# BaseCutout.net
KiCad netlist of a schematic drawn in EAGLE
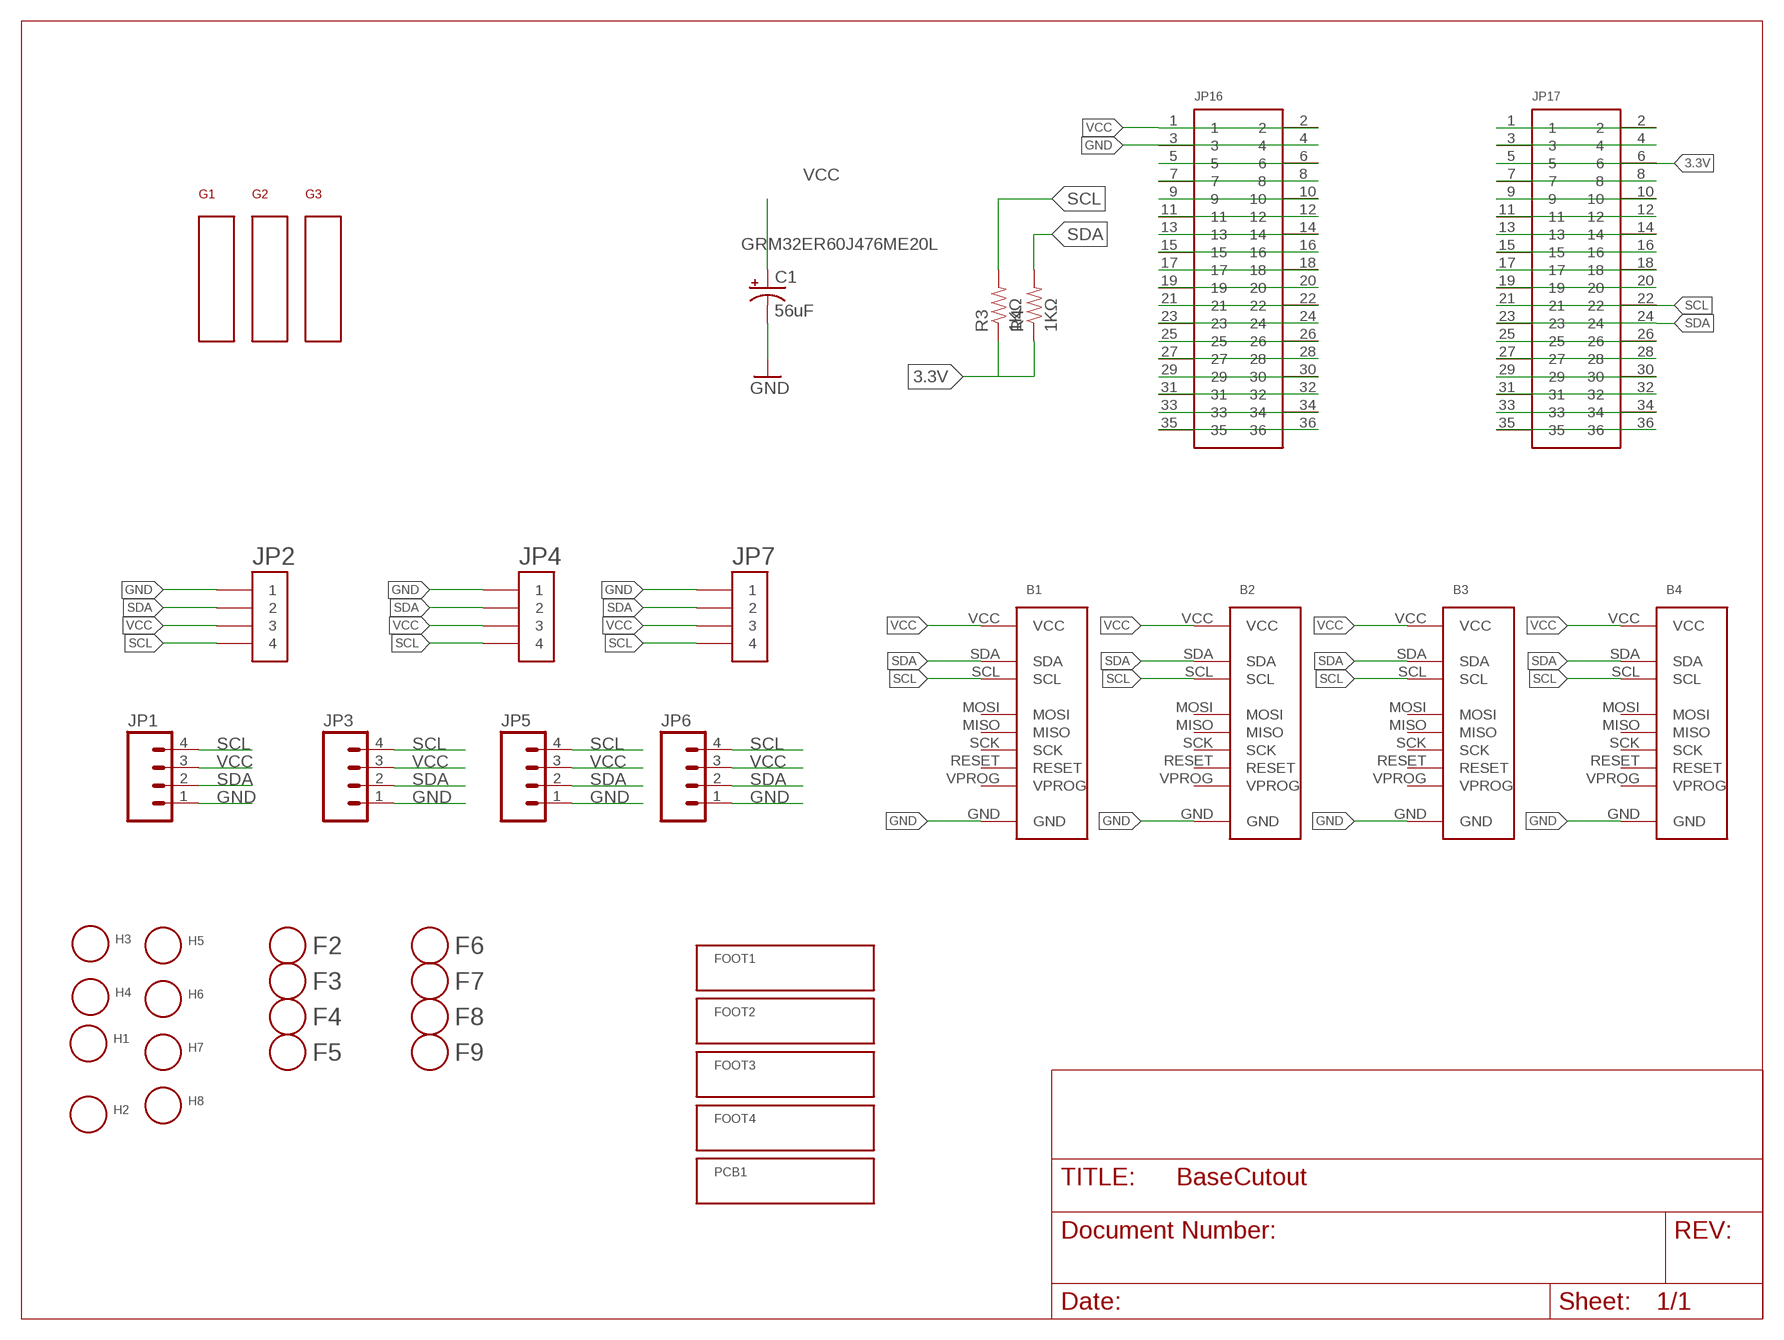
[diagram p0: schematic, sheet 1]

(export (version "E")
  (design (tool "Eeschema 10.0.6"))
  (components
    (comp (ref "B1")
      (value "BASE-PADS")
      (footprint "eagle-import:BASE-PADS")
      (libsource (lib "eagle-import") (part "BASE-PADS"))
    )
    (comp (ref "B2")
      (value "BASE-PADS")
      (footprint "eagle-import:BASE-PADS")
      (libsource (lib "eagle-import") (part "BASE-PADS"))
    )
    (comp (ref "B3")
      (value "BASE-PADS")
      (footprint "eagle-import:BASE-PADS")
      (libsource (lib "eagle-import") (part "BASE-PADS"))
    )
    (comp (ref "B4")
      (value "BASE-PADS")
      (footprint "eagle-import:BASE-PADS")
      (libsource (lib "eagle-import") (part "BASE-PADS"))
    )
    (comp (ref "C1")
      (value "56uF")
      (footprint "eagle-import:PANASONIC_D")
      (fields (field (name "PARTNUM") "EMVA250ADA560MF55G"))
      (libsource (lib "eagle-import") (part "CAPACITOR-POL-56UF-25V"))
    )
    (comp (ref "F2")
      (value "FIDUCIAL")
      (footprint "eagle-import:FIDUCIAL_1MM")
      (libsource (lib "eagle-import") (part "FIDUCIAL"))
    )
    (comp (ref "F3")
      (value "FIDUCIAL")
      (footprint "eagle-import:FIDUCIAL_1MM")
      (libsource (lib "eagle-import") (part "FIDUCIAL"))
    )
    (comp (ref "F4")
      (value "FIDUCIAL")
      (footprint "eagle-import:FIDUCIAL_1MM")
      (libsource (lib "eagle-import") (part "FIDUCIAL"))
    )
    (comp (ref "F5")
      (value "FIDUCIAL")
      (footprint "eagle-import:FIDUCIAL_1MM")
      (libsource (lib "eagle-import") (part "FIDUCIAL"))
    )
    (comp (ref "F6")
      (value "FIDUCIAL")
      (footprint "eagle-import:FIDUCIAL_1MM")
      (libsource (lib "eagle-import") (part "FIDUCIAL"))
    )
    (comp (ref "F7")
      (value "FIDUCIAL")
      (footprint "eagle-import:FIDUCIAL_1MM")
      (libsource (lib "eagle-import") (part "FIDUCIAL"))
    )
    (comp (ref "F8")
      (value "FIDUCIAL")
      (footprint "eagle-import:FIDUCIAL_1MM")
      (libsource (lib "eagle-import") (part "FIDUCIAL"))
    )
    (comp (ref "F9")
      (value "FIDUCIAL")
      (footprint "eagle-import:FIDUCIAL_1MM")
      (libsource (lib "eagle-import") (part "FIDUCIAL"))
    )
    (comp (ref "G1")
      (value "CARD-GUIDE")
      (footprint "eagle-import:CARD-GUIDE-2_")
      (fields (field (name "PARTNUM") "HCG-201-165"))
      (libsource (lib "eagle-import") (part "CARD-GUIDE"))
    )
    (comp (ref "G2")
      (value "CARD-GUIDE")
      (footprint "eagle-import:CARD-GUIDE-2_")
      (fields (field (name "PARTNUM") "HCG-202-165"))
      (libsource (lib "eagle-import") (part "CARD-GUIDE"))
    )
    (comp (ref "G3")
      (value "CARD-GUIDE")
      (footprint "eagle-import:CARD-GUIDE-2_")
      (fields (field (name "PARTNUM") "HCG-201-165"))
      (libsource (lib "eagle-import") (part "CARD-GUIDE"))
    )
    (comp (ref "H1")
      (value "HOLE#2")
      (footprint "eagle-import:HOLE-#2")
      (fields (field (name "PARTNUM") "EXCLUDE"))
      (libsource (lib "eagle-import") (part "HOLE#2"))
    )
    (comp (ref "H2")
      (value "HOLE#2")
      (footprint "eagle-import:HOLE-#2")
      (fields (field (name "PARTNUM") "EXCLUDE"))
      (libsource (lib "eagle-import") (part "HOLE#2"))
    )
    (comp (ref "H3")
      (value "HOLE#2")
      (footprint "eagle-import:HOLE-#2")
      (fields (field (name "PARTNUM") "EXCLUDE"))
      (libsource (lib "eagle-import") (part "HOLE#2"))
    )
    (comp (ref "H4")
      (value "HOLE#2")
      (footprint "eagle-import:HOLE-#2")
      (fields (field (name "PARTNUM") "EXCLUDE"))
      (libsource (lib "eagle-import") (part "HOLE#2"))
    )
    (comp (ref "H5")
      (value "HOLE#2")
      (footprint "eagle-import:HOLE-#2")
      (fields (field (name "PARTNUM") "EXCLUDE"))
      (libsource (lib "eagle-import") (part "HOLE#2"))
    )
    (comp (ref "H6")
      (value "HOLE#2")
      (footprint "eagle-import:HOLE-#2")
      (fields (field (name "PARTNUM") "EXCLUDE"))
      (libsource (lib "eagle-import") (part "HOLE#2"))
    )
    (comp (ref "H7")
      (value "HOLE#2")
      (footprint "eagle-import:HOLE-#2")
      (fields (field (name "PARTNUM") "EXCLUDE"))
      (libsource (lib "eagle-import") (part "HOLE#2"))
    )
    (comp (ref "H8")
      (value "HOLE#2")
      (footprint "eagle-import:HOLE-#2")
      (fields (field (name "PARTNUM") "EXCLUDE"))
      (libsource (lib "eagle-import") (part "HOLE#2"))
    )
    (comp (ref "JP1")
      (value "M04LOCK")
      (footprint "eagle-import:1X04_LOCK")
      (fields (field (name "PARTNUM") "M20-9750446"))
      (libsource (lib "eagle-import") (part "M04LOCK"))
    )
    (comp (ref "JP2")
      (value "HEADER-1X4-JST-PA-TOP-SMD")
      (footprint "eagle-import:JST-PA-TOP-SMD")
      (fields (field (name "PARTNUM") "SM04B-PASS-TBT(LF)(SN)"))
      (libsource (lib "eagle-import") (part "HEADER-1X4-JST-PA-TOP-SMD"))
    )
    (comp (ref "JP3")
      (value "M04LOCK")
      (footprint "eagle-import:1X04_LOCK")
      (fields (field (name "PARTNUM") "M20-9750446"))
      (libsource (lib "eagle-import") (part "M04LOCK"))
    )
    (comp (ref "JP4")
      (value "HEADER-1X4-JST-PA-TOP-SMD")
      (footprint "eagle-import:JST-PA-TOP-SMD")
      (fields (field (name "PARTNUM") "SM04B-PASS-TBT(LF)(SN)"))
      (libsource (lib "eagle-import") (part "HEADER-1X4-JST-PA-TOP-SMD"))
    )
    (comp (ref "JP5")
      (value "M04LOCK")
      (footprint "eagle-import:1X04_LOCK")
      (fields (field (name "PARTNUM") "M20-9750446"))
      (libsource (lib "eagle-import") (part "M04LOCK"))
    )
    (comp (ref "JP6")
      (value "M04LOCK")
      (footprint "eagle-import:1X04_LOCK")
      (fields (field (name "PARTNUM") "M20-9750446"))
      (libsource (lib "eagle-import") (part "M04LOCK"))
    )
    (comp (ref "JP7")
      (value "HEADER-1X4-JST-PA-TOP-SMD")
      (footprint "eagle-import:JST-PA-TOP-SMD")
      (fields (field (name "PARTNUM") "SM04B-PASS-TBT(LF)(SN)"))
      (libsource (lib "eagle-import") (part "HEADER-1X4-JST-PA-TOP-SMD"))
    )
    (comp (ref "JP16")
      (value "HEADER-2X18")
      (footprint "eagle-import:2X18-LOCK")
      (fields (field (name "PARTNUM") "PPTC182LFBN-RC"))
      (libsource (lib "eagle-import") (part "HEADER-2X18"))
    )
    (comp (ref "JP17")
      (value "HEADER-2X18")
      (footprint "eagle-import:2X18-LOCK")
      (fields (field (name "PARTNUM") "PPTC182LFBN-RC"))
      (libsource (lib "eagle-import") (part "HEADER-2X18"))
    )
    (comp (ref "R3")
      (value "1KΩ")
      (footprint "eagle-import:0603")
      (fields (field (name "PARTNUM") "ERJ-3EKF1001V"))
      (libsource (lib "eagle-import") (part "RESISTOR-1KΩ"))
    )
    (comp (ref "R4")
      (value "1KΩ")
      (footprint "eagle-import:0603")
      (fields (field (name "PARTNUM") "ERJ-3EKF1001V"))
      (libsource (lib "eagle-import") (part "RESISTOR-1KΩ"))
    )
  )
  (nets
    (net (code "1") (name "3.3V") (class "Default")
      (node (ref "JP17") (pin "5") (pinfunction "5_5") (pintype "bidirectional"))
      (node (ref "JP17") (pin "6") (pinfunction "6_6") (pintype "bidirectional"))
      (node (ref "R3") (pin "1") (pinfunction "1_1") (pintype "passive"))
      (node (ref "R4") (pin "1") (pinfunction "1_1") (pintype "passive"))
    )
    (net (code "2") (name "GND") (class "Default")
      (node (ref "B1") (pin "GND") (pinfunction "GND_GND") (pintype "bidirectional"))
      (node (ref "B2") (pin "GND") (pinfunction "GND_GND") (pintype "bidirectional"))
      (node (ref "B3") (pin "GND") (pinfunction "GND_GND") (pintype "bidirectional"))
      (node (ref "B4") (pin "GND") (pinfunction "GND_GND") (pintype "bidirectional"))
      (node (ref "C1") (pin "-") (pinfunction "-_-") (pintype "passive"))
      (node (ref "JP1") (pin "1") (pinfunction "1_1") (pintype "passive"))
      (node (ref "JP16") (pin "3") (pinfunction "3_3") (pintype "bidirectional"))
      (node (ref "JP16") (pin "4") (pinfunction "4_4") (pintype "bidirectional"))
      (node (ref "JP2") (pin "1") (pinfunction "1_1") (pintype "bidirectional"))
      (node (ref "JP3") (pin "1") (pinfunction "1_1") (pintype "passive"))
      (node (ref "JP4") (pin "1") (pinfunction "1_1") (pintype "bidirectional"))
      (node (ref "JP5") (pin "1") (pinfunction "1_1") (pintype "passive"))
      (node (ref "JP6") (pin "1") (pinfunction "1_1") (pintype "passive"))
      (node (ref "JP7") (pin "1") (pinfunction "1_1") (pintype "bidirectional"))
    )
    (net (code "3") (name "Net-(JP16-Pad5)") (class "Default")
      (node (ref "JP16") (pin "5") (pinfunction "5_5") (pintype "bidirectional"))
      (node (ref "JP16") (pin "6") (pinfunction "6_6") (pintype "bidirectional"))
    )
    (net (code "4") (name "Net-(JP16-Pad7)") (class "Default")
      (node (ref "JP16") (pin "7") (pinfunction "7_7") (pintype "bidirectional"))
      (node (ref "JP16") (pin "8") (pinfunction "8_8") (pintype "bidirectional"))
    )
    (net (code "5") (name "Net-(JP16-Pad10)") (class "Default")
      (node (ref "JP16") (pin "10") (pinfunction "10_10") (pintype "bidirectional"))
      (node (ref "JP16") (pin "9") (pinfunction "9_9") (pintype "bidirectional"))
    )
    (net (code "6") (name "Net-(JP16-Pad11)") (class "Default")
      (node (ref "JP16") (pin "11") (pinfunction "11_11") (pintype "bidirectional"))
      (node (ref "JP16") (pin "12") (pinfunction "12_12") (pintype "bidirectional"))
    )
    (net (code "7") (name "Net-(JP16-Pad13)") (class "Default")
      (node (ref "JP16") (pin "13") (pinfunction "13_13") (pintype "bidirectional"))
      (node (ref "JP16") (pin "14") (pinfunction "14_14") (pintype "bidirectional"))
    )
    (net (code "8") (name "Net-(JP16-Pad15)") (class "Default")
      (node (ref "JP16") (pin "15") (pinfunction "15_15") (pintype "bidirectional"))
      (node (ref "JP16") (pin "16") (pinfunction "16_16") (pintype "bidirectional"))
    )
    (net (code "9") (name "Net-(JP16-Pad17)") (class "Default")
      (node (ref "JP16") (pin "17") (pinfunction "17_17") (pintype "bidirectional"))
      (node (ref "JP16") (pin "18") (pinfunction "18_18") (pintype "bidirectional"))
    )
    (net (code "10") (name "Net-(JP16-Pad19)") (class "Default")
      (node (ref "JP16") (pin "19") (pinfunction "19_19") (pintype "bidirectional"))
      (node (ref "JP16") (pin "20") (pinfunction "20_20") (pintype "bidirectional"))
    )
    (net (code "11") (name "Net-(JP16-Pad21)") (class "Default")
      (node (ref "JP16") (pin "21") (pinfunction "21_21") (pintype "bidirectional"))
      (node (ref "JP16") (pin "22") (pinfunction "22_22") (pintype "bidirectional"))
    )
    (net (code "12") (name "Net-(JP16-Pad23)") (class "Default")
      (node (ref "JP16") (pin "23") (pinfunction "23_23") (pintype "bidirectional"))
      (node (ref "JP16") (pin "24") (pinfunction "24_24") (pintype "bidirectional"))
    )
    (net (code "13") (name "Net-(JP16-Pad25)") (class "Default")
      (node (ref "JP16") (pin "25") (pinfunction "25_25") (pintype "bidirectional"))
      (node (ref "JP16") (pin "26") (pinfunction "26_26") (pintype "bidirectional"))
    )
    (net (code "14") (name "Net-(JP16-Pad27)") (class "Default")
      (node (ref "JP16") (pin "27") (pinfunction "27_27") (pintype "bidirectional"))
      (node (ref "JP16") (pin "28") (pinfunction "28_28") (pintype "bidirectional"))
    )
    (net (code "15") (name "Net-(JP16-Pad29)") (class "Default")
      (node (ref "JP16") (pin "29") (pinfunction "29_29") (pintype "bidirectional"))
      (node (ref "JP16") (pin "30") (pinfunction "30_30") (pintype "bidirectional"))
    )
    (net (code "16") (name "Net-(JP16-Pad31)") (class "Default")
      (node (ref "JP16") (pin "31") (pinfunction "31_31") (pintype "bidirectional"))
      (node (ref "JP16") (pin "32") (pinfunction "32_32") (pintype "bidirectional"))
    )
    (net (code "17") (name "Net-(JP16-Pad33)") (class "Default")
      (node (ref "JP16") (pin "33") (pinfunction "33_33") (pintype "bidirectional"))
      (node (ref "JP16") (pin "34") (pinfunction "34_34") (pintype "bidirectional"))
    )
    (net (code "18") (name "Net-(JP16-Pad35)") (class "Default")
      (node (ref "JP16") (pin "35") (pinfunction "35_35") (pintype "bidirectional"))
      (node (ref "JP16") (pin "36") (pinfunction "36_36") (pintype "bidirectional"))
    )
    (net (code "19") (name "Net-(JP17-Pad1)") (class "Default")
      (node (ref "JP17") (pin "1") (pinfunction "1_1") (pintype "bidirectional"))
      (node (ref "JP17") (pin "2") (pinfunction "2_2") (pintype "bidirectional"))
    )
    (net (code "20") (name "Net-(JP17-Pad3)") (class "Default")
      (node (ref "JP17") (pin "3") (pinfunction "3_3") (pintype "bidirectional"))
      (node (ref "JP17") (pin "4") (pinfunction "4_4") (pintype "bidirectional"))
    )
    (net (code "21") (name "Net-(JP17-Pad7)") (class "Default")
      (node (ref "JP17") (pin "7") (pinfunction "7_7") (pintype "bidirectional"))
      (node (ref "JP17") (pin "8") (pinfunction "8_8") (pintype "bidirectional"))
    )
    (net (code "22") (name "Net-(JP17-Pad10)") (class "Default")
      (node (ref "JP17") (pin "10") (pinfunction "10_10") (pintype "bidirectional"))
      (node (ref "JP17") (pin "9") (pinfunction "9_9") (pintype "bidirectional"))
    )
    (net (code "23") (name "Net-(JP17-Pad11)") (class "Default")
      (node (ref "JP17") (pin "11") (pinfunction "11_11") (pintype "bidirectional"))
      (node (ref "JP17") (pin "12") (pinfunction "12_12") (pintype "bidirectional"))
    )
    (net (code "24") (name "Net-(JP17-Pad13)") (class "Default")
      (node (ref "JP17") (pin "13") (pinfunction "13_13") (pintype "bidirectional"))
      (node (ref "JP17") (pin "14") (pinfunction "14_14") (pintype "bidirectional"))
    )
    (net (code "25") (name "Net-(JP17-Pad15)") (class "Default")
      (node (ref "JP17") (pin "15") (pinfunction "15_15") (pintype "bidirectional"))
      (node (ref "JP17") (pin "16") (pinfunction "16_16") (pintype "bidirectional"))
    )
    (net (code "26") (name "Net-(JP17-Pad17)") (class "Default")
      (node (ref "JP17") (pin "17") (pinfunction "17_17") (pintype "bidirectional"))
      (node (ref "JP17") (pin "18") (pinfunction "18_18") (pintype "bidirectional"))
    )
    (net (code "27") (name "Net-(JP17-Pad19)") (class "Default")
      (node (ref "JP17") (pin "19") (pinfunction "19_19") (pintype "bidirectional"))
      (node (ref "JP17") (pin "20") (pinfunction "20_20") (pintype "bidirectional"))
    )
    (net (code "28") (name "Net-(JP17-Pad25)") (class "Default")
      (node (ref "JP17") (pin "25") (pinfunction "25_25") (pintype "bidirectional"))
      (node (ref "JP17") (pin "26") (pinfunction "26_26") (pintype "bidirectional"))
    )
    (net (code "29") (name "Net-(JP17-Pad27)") (class "Default")
      (node (ref "JP17") (pin "27") (pinfunction "27_27") (pintype "bidirectional"))
      (node (ref "JP17") (pin "28") (pinfunction "28_28") (pintype "bidirectional"))
    )
    (net (code "30") (name "Net-(JP17-Pad29)") (class "Default")
      (node (ref "JP17") (pin "29") (pinfunction "29_29") (pintype "bidirectional"))
      (node (ref "JP17") (pin "30") (pinfunction "30_30") (pintype "bidirectional"))
    )
    (net (code "31") (name "Net-(JP17-Pad31)") (class "Default")
      (node (ref "JP17") (pin "31") (pinfunction "31_31") (pintype "bidirectional"))
      (node (ref "JP17") (pin "32") (pinfunction "32_32") (pintype "bidirectional"))
    )
    (net (code "32") (name "Net-(JP17-Pad33)") (class "Default")
      (node (ref "JP17") (pin "33") (pinfunction "33_33") (pintype "bidirectional"))
      (node (ref "JP17") (pin "34") (pinfunction "34_34") (pintype "bidirectional"))
    )
    (net (code "33") (name "Net-(JP17-Pad35)") (class "Default")
      (node (ref "JP17") (pin "35") (pinfunction "35_35") (pintype "bidirectional"))
      (node (ref "JP17") (pin "36") (pinfunction "36_36") (pintype "bidirectional"))
    )
    (net (code "34") (name "SCL") (class "Default")
      (node (ref "B1") (pin "SCL") (pinfunction "SCL_SCL") (pintype "bidirectional"))
      (node (ref "B2") (pin "SCL") (pinfunction "SCL_SCL") (pintype "bidirectional"))
      (node (ref "B3") (pin "SCL") (pinfunction "SCL_SCL") (pintype "bidirectional"))
      (node (ref "B4") (pin "SCL") (pinfunction "SCL_SCL") (pintype "bidirectional"))
      (node (ref "JP1") (pin "4") (pinfunction "4_4") (pintype "passive"))
      (node (ref "JP17") (pin "21") (pinfunction "21_21") (pintype "bidirectional"))
      (node (ref "JP17") (pin "22") (pinfunction "22_22") (pintype "bidirectional"))
      (node (ref "JP2") (pin "4") (pinfunction "4_4") (pintype "bidirectional"))
      (node (ref "JP3") (pin "4") (pinfunction "4_4") (pintype "passive"))
      (node (ref "JP4") (pin "4") (pinfunction "4_4") (pintype "bidirectional"))
      (node (ref "JP5") (pin "4") (pinfunction "4_4") (pintype "passive"))
      (node (ref "JP6") (pin "4") (pinfunction "4_4") (pintype "passive"))
      (node (ref "JP7") (pin "4") (pinfunction "4_4") (pintype "bidirectional"))
      (node (ref "R3") (pin "2") (pinfunction "2_2") (pintype "passive"))
    )
    (net (code "35") (name "SDA") (class "Default")
      (node (ref "B1") (pin "SDA") (pinfunction "SDA_SDA") (pintype "bidirectional"))
      (node (ref "B2") (pin "SDA") (pinfunction "SDA_SDA") (pintype "bidirectional"))
      (node (ref "B3") (pin "SDA") (pinfunction "SDA_SDA") (pintype "bidirectional"))
      (node (ref "B4") (pin "SDA") (pinfunction "SDA_SDA") (pintype "bidirectional"))
      (node (ref "JP1") (pin "2") (pinfunction "2_2") (pintype "passive"))
      (node (ref "JP17") (pin "23") (pinfunction "23_23") (pintype "bidirectional"))
      (node (ref "JP17") (pin "24") (pinfunction "24_24") (pintype "bidirectional"))
      (node (ref "JP2") (pin "2") (pinfunction "2_2") (pintype "bidirectional"))
      (node (ref "JP3") (pin "2") (pinfunction "2_2") (pintype "passive"))
      (node (ref "JP4") (pin "2") (pinfunction "2_2") (pintype "bidirectional"))
      (node (ref "JP5") (pin "2") (pinfunction "2_2") (pintype "passive"))
      (node (ref "JP6") (pin "2") (pinfunction "2_2") (pintype "passive"))
      (node (ref "JP7") (pin "2") (pinfunction "2_2") (pintype "bidirectional"))
      (node (ref "R4") (pin "2") (pinfunction "2_2") (pintype "passive"))
    )
    (net (code "36") (name "VCC") (class "Default")
      (node (ref "B1") (pin "VCC") (pinfunction "VCC_VCC") (pintype "bidirectional"))
      (node (ref "B2") (pin "VCC") (pinfunction "VCC_VCC") (pintype "bidirectional"))
      (node (ref "B3") (pin "VCC") (pinfunction "VCC_VCC") (pintype "bidirectional"))
      (node (ref "B4") (pin "VCC") (pinfunction "VCC_VCC") (pintype "bidirectional"))
      (node (ref "C1") (pin "+") (pinfunction "+_+") (pintype "passive"))
      (node (ref "JP1") (pin "3") (pinfunction "3_3") (pintype "passive"))
      (node (ref "JP16") (pin "1") (pinfunction "1_1") (pintype "bidirectional"))
      (node (ref "JP16") (pin "2") (pinfunction "2_2") (pintype "bidirectional"))
      (node (ref "JP2") (pin "3") (pinfunction "3_3") (pintype "bidirectional"))
      (node (ref "JP3") (pin "3") (pinfunction "3_3") (pintype "passive"))
      (node (ref "JP4") (pin "3") (pinfunction "3_3") (pintype "bidirectional"))
      (node (ref "JP5") (pin "3") (pinfunction "3_3") (pintype "passive"))
      (node (ref "JP6") (pin "3") (pinfunction "3_3") (pintype "passive"))
      (node (ref "JP7") (pin "3") (pinfunction "3_3") (pintype "bidirectional"))
    )
    (net (code "37") (name "unconnected-(B1-PadMISO)") (class "Default")
      (node (ref "B1") (pin "MISO") (pinfunction "MISO_MISO") (pintype "bidirectional"))
    )
    (net (code "38") (name "unconnected-(B1-PadMOSI)") (class "Default")
      (node (ref "B1") (pin "MOSI") (pinfunction "MOSI_MOSI") (pintype "bidirectional"))
    )
    (net (code "39") (name "unconnected-(B1-PadRESET)") (class "Default")
      (node (ref "B1") (pin "RESET") (pinfunction "RESET_RESET") (pintype "bidirectional"))
    )
    (net (code "40") (name "unconnected-(B1-PadSCK)") (class "Default")
      (node (ref "B1") (pin "SCK") (pinfunction "SCK_SCK") (pintype "bidirectional"))
    )
    (net (code "41") (name "unconnected-(B1-PadVPROG)") (class "Default")
      (node (ref "B1") (pin "VPROG") (pinfunction "VPROG_VPROG") (pintype "bidirectional"))
    )
    (net (code "42") (name "unconnected-(B2-PadMISO)") (class "Default")
      (node (ref "B2") (pin "MISO") (pinfunction "MISO_MISO") (pintype "bidirectional"))
    )
    (net (code "43") (name "unconnected-(B2-PadMOSI)") (class "Default")
      (node (ref "B2") (pin "MOSI") (pinfunction "MOSI_MOSI") (pintype "bidirectional"))
    )
    (net (code "44") (name "unconnected-(B2-PadRESET)") (class "Default")
      (node (ref "B2") (pin "RESET") (pinfunction "RESET_RESET") (pintype "bidirectional"))
    )
    (net (code "45") (name "unconnected-(B2-PadSCK)") (class "Default")
      (node (ref "B2") (pin "SCK") (pinfunction "SCK_SCK") (pintype "bidirectional"))
    )
    (net (code "46") (name "unconnected-(B2-PadVPROG)") (class "Default")
      (node (ref "B2") (pin "VPROG") (pinfunction "VPROG_VPROG") (pintype "bidirectional"))
    )
    (net (code "47") (name "unconnected-(B3-PadMISO)") (class "Default")
      (node (ref "B3") (pin "MISO") (pinfunction "MISO_MISO") (pintype "bidirectional"))
    )
    (net (code "48") (name "unconnected-(B3-PadMOSI)") (class "Default")
      (node (ref "B3") (pin "MOSI") (pinfunction "MOSI_MOSI") (pintype "bidirectional"))
    )
    (net (code "49") (name "unconnected-(B3-PadRESET)") (class "Default")
      (node (ref "B3") (pin "RESET") (pinfunction "RESET_RESET") (pintype "bidirectional"))
    )
    (net (code "50") (name "unconnected-(B3-PadSCK)") (class "Default")
      (node (ref "B3") (pin "SCK") (pinfunction "SCK_SCK") (pintype "bidirectional"))
    )
    (net (code "51") (name "unconnected-(B3-PadVPROG)") (class "Default")
      (node (ref "B3") (pin "VPROG") (pinfunction "VPROG_VPROG") (pintype "bidirectional"))
    )
    (net (code "52") (name "unconnected-(B4-PadMISO)") (class "Default")
      (node (ref "B4") (pin "MISO") (pinfunction "MISO_MISO") (pintype "bidirectional"))
    )
    (net (code "53") (name "unconnected-(B4-PadMOSI)") (class "Default")
      (node (ref "B4") (pin "MOSI") (pinfunction "MOSI_MOSI") (pintype "bidirectional"))
    )
    (net (code "54") (name "unconnected-(B4-PadRESET)") (class "Default")
      (node (ref "B4") (pin "RESET") (pinfunction "RESET_RESET") (pintype "bidirectional"))
    )
    (net (code "55") (name "unconnected-(B4-PadSCK)") (class "Default")
      (node (ref "B4") (pin "SCK") (pinfunction "SCK_SCK") (pintype "bidirectional"))
    )
    (net (code "56") (name "unconnected-(B4-PadVPROG)") (class "Default")
      (node (ref "B4") (pin "VPROG") (pinfunction "VPROG_VPROG") (pintype "bidirectional"))
    )
    (net (code "57") (name "unconnected-(H1-HOLE-PadP$1)") (class "Default")
      (node (ref "H1") (pin "P$1") (pinfunction "HOLE_P$1") (pintype "bidirectional"))
    )
    (net (code "58") (name "unconnected-(H2-HOLE-PadP$1)") (class "Default")
      (node (ref "H2") (pin "P$1") (pinfunction "HOLE_P$1") (pintype "bidirectional"))
    )
    (net (code "59") (name "unconnected-(H3-HOLE-PadP$1)") (class "Default")
      (node (ref "H3") (pin "P$1") (pinfunction "HOLE_P$1") (pintype "bidirectional"))
    )
    (net (code "60") (name "unconnected-(H4-HOLE-PadP$1)") (class "Default")
      (node (ref "H4") (pin "P$1") (pinfunction "HOLE_P$1") (pintype "bidirectional"))
    )
    (net (code "61") (name "unconnected-(H5-HOLE-PadP$1)") (class "Default")
      (node (ref "H5") (pin "P$1") (pinfunction "HOLE_P$1") (pintype "bidirectional"))
    )
    (net (code "62") (name "unconnected-(H6-HOLE-PadP$1)") (class "Default")
      (node (ref "H6") (pin "P$1") (pinfunction "HOLE_P$1") (pintype "bidirectional"))
    )
    (net (code "63") (name "unconnected-(H7-HOLE-PadP$1)") (class "Default")
      (node (ref "H7") (pin "P$1") (pinfunction "HOLE_P$1") (pintype "bidirectional"))
    )
    (net (code "64") (name "unconnected-(H8-HOLE-PadP$1)") (class "Default")
      (node (ref "H8") (pin "P$1") (pinfunction "HOLE_P$1") (pintype "bidirectional"))
    )
  )
)
